# side_panel_V5_2.net
KiCad netlist of a schematic drawn in EAGLE
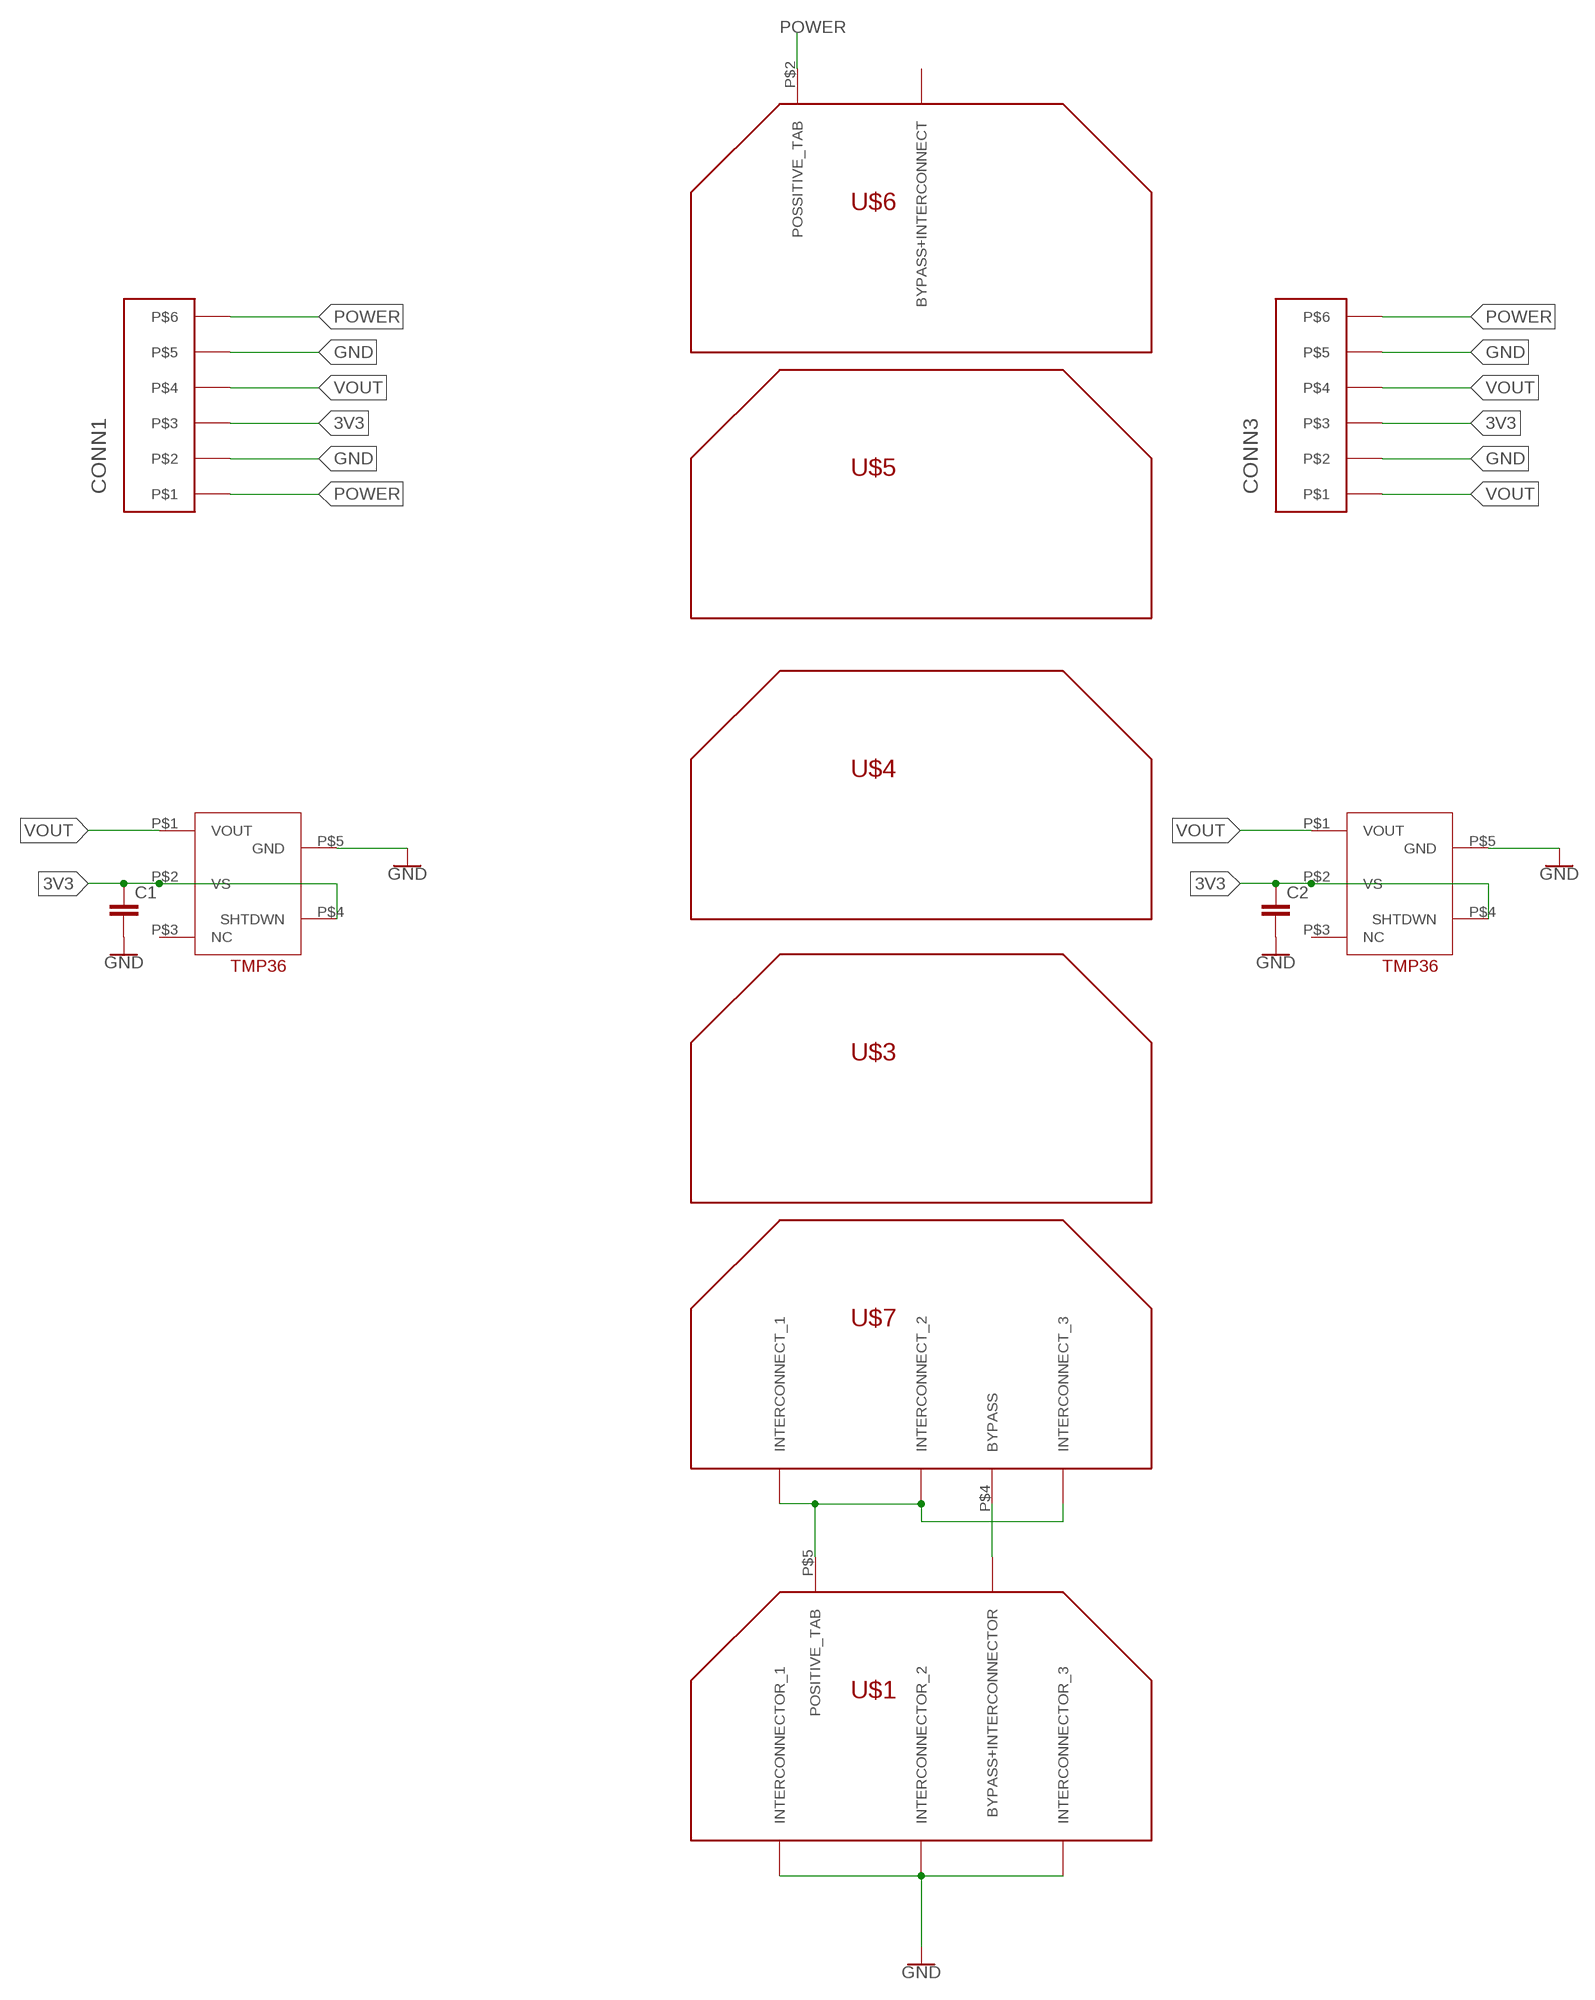
[diagram p0: schematic, sheet 1]

(export (version "E")
  (design (tool "Eeschema 10.0.6"))
  (components
    (comp (ref "C1")
      (value "CAPACITOR0805")
      (footprint "eagle-import:0805")
      (libsource (lib "eagle-import") (part "CAPACITOR0805"))
    )
    (comp (ref "C2")
      (value "CAPACITOR0805")
      (footprint "eagle-import:0805")
      (libsource (lib "eagle-import") (part "CAPACITOR0805"))
    )
    (comp (ref "CONN1")
      (value "PICOLOCK_6")
      (footprint "eagle-import:PICOLOCK_6")
      (libsource (lib "eagle-import") (part "PICOLOCK_6"))
    )
    (comp (ref "CONN3")
      (value "PICOLOCK_6")
      (footprint "eagle-import:PICOLOCK_6")
      (libsource (lib "eagle-import") (part "PICOLOCK_6"))
    )
    (comp (ref "U$1")
      (value "SOLAR_CELL_STAND-ALONE")
      (footprint "eagle-import:SOLAR_CELL_STAND-ALONE")
      (libsource (lib "eagle-import") (part "SOLAR_CELL_STAND-ALONE"))
    )
    (comp (ref "U$2")
      (value "TMP36")
      (footprint "eagle-import:SOT-23-5")
      (libsource (lib "eagle-import") (part "TMP36"))
    )
    (comp (ref "U$3")
      (value "SOALAR_CELL_OUTLINE")
      (footprint "eagle-import:SOLAR_CELL_OUTLINE")
      (libsource (lib "eagle-import") (part "SOALAR_CELL_OUTLINE"))
    )
    (comp (ref "U$4")
      (value "SOALAR_CELL_OUTLINE")
      (footprint "eagle-import:SOLAR_CELL_OUTLINE")
      (libsource (lib "eagle-import") (part "SOALAR_CELL_OUTLINE"))
    )
    (comp (ref "U$5")
      (value "SOALAR_CELL_OUTLINE")
      (footprint "eagle-import:SOLAR_CELL_OUTLINE")
      (libsource (lib "eagle-import") (part "SOALAR_CELL_OUTLINE"))
    )
    (comp (ref "U$6")
      (value "SOLAR_CELL_TOP")
      (footprint "eagle-import:SOLAR_CELL_TOP_SHORT-PAD")
      (libsource (lib "eagle-import") (part "SOLAR_CELL_TOP"))
    )
    (comp (ref "U$7")
      (value "SOLAR_CELL_BOTTOM+BYPASS")
      (footprint "eagle-import:SOLAR_CELL_BOTTOM+BYPASS")
      (libsource (lib "eagle-import") (part "SOLAR_CELL_BOTTOM+BYPASS"))
    )
    (comp (ref "U$8")
      (value "TMP36")
      (footprint "eagle-import:SOT-23-5")
      (libsource (lib "eagle-import") (part "TMP36"))
    )
  )
  (nets
    (net (code "1") (name "3V3") (class "Default")
      (node (ref "C1") (pin "1") (pinfunction "1_1") (pintype "passive"))
      (node (ref "C2") (pin "1") (pinfunction "1_1") (pintype "passive"))
      (node (ref "CONN1") (pin "P$3") (pinfunction "P$3_P$3") (pintype "bidirectional"))
      (node (ref "CONN3") (pin "P$3") (pinfunction "P$3_P$3") (pintype "bidirectional"))
      (node (ref "U$2") (pin "P$2") (pinfunction "VS_P$2") (pintype "bidirectional"))
      (node (ref "U$2") (pin "P$4") (pinfunction "SHTDWN_P$4") (pintype "bidirectional"))
      (node (ref "U$8") (pin "P$2") (pinfunction "VS_P$2") (pintype "bidirectional"))
      (node (ref "U$8") (pin "P$4") (pinfunction "SHTDWN_P$4") (pintype "bidirectional"))
    )
    (net (code "2") (name "GND") (class "Default")
      (node (ref "C1") (pin "2") (pinfunction "2_2") (pintype "passive"))
      (node (ref "C2") (pin "2") (pinfunction "2_2") (pintype "passive"))
      (node (ref "CONN1") (pin "P$2") (pinfunction "P$2_P$2") (pintype "bidirectional"))
      (node (ref "CONN1") (pin "P$5") (pinfunction "P$5_P$5") (pintype "bidirectional"))
      (node (ref "CONN3") (pin "P$2") (pinfunction "P$2_P$2") (pintype "bidirectional"))
      (node (ref "CONN3") (pin "P$5") (pinfunction "P$5_P$5") (pintype "bidirectional"))
      (node (ref "U$1") (pin "P$1") (pinfunction "INTERCONNECTOR_1_P$1") (pintype "bidirectional"))
      (node (ref "U$1") (pin "P$2") (pinfunction "INTERCONNECTOR_2_P$2") (pintype "bidirectional"))
      (node (ref "U$1") (pin "P$3") (pinfunction "INTERCONNECTOR_3_P$3") (pintype "bidirectional"))
      (node (ref "U$2") (pin "P$5") (pinfunction "GND_P$5") (pintype "bidirectional"))
      (node (ref "U$8") (pin "P$5") (pinfunction "GND_P$5") (pintype "bidirectional"))
    )
    (net (code "3") (name "Net-(U$1-BYPASS+INTERCONNECTOR)") (class "Default")
      (node (ref "U$1") (pin "P$4") (pinfunction "BYPASS+INTERCONNECTOR_P$4") (pintype "bidirectional"))
      (node (ref "U$7") (pin "P$4") (pinfunction "BYPASS_P$4") (pintype "bidirectional"))
    )
    (net (code "4") (name "Net-(U$1-POSITIVE_TAB)") (class "Default")
      (node (ref "U$1") (pin "P$5") (pinfunction "POSITIVE_TAB_P$5") (pintype "bidirectional"))
      (node (ref "U$7") (pin "P$1") (pinfunction "INTERCONNECT_1_P$1") (pintype "bidirectional"))
      (node (ref "U$7") (pin "P$2") (pinfunction "INTERCONNECT_2_P$2") (pintype "bidirectional"))
      (node (ref "U$7") (pin "P$3") (pinfunction "INTERCONNECT_3_P$3") (pintype "bidirectional"))
    )
    (net (code "5") (name "POWER") (class "Default")
      (node (ref "CONN1") (pin "P$1") (pinfunction "P$1_P$1") (pintype "bidirectional"))
      (node (ref "CONN1") (pin "P$6") (pinfunction "P$6_P$6") (pintype "bidirectional"))
      (node (ref "CONN3") (pin "P$6") (pinfunction "P$6_P$6") (pintype "bidirectional"))
      (node (ref "U$6") (pin "P$2") (pinfunction "POSSITIVE_TAB_P$2") (pintype "bidirectional"))
    )
    (net (code "6") (name "VOUT") (class "Default")
      (node (ref "CONN1") (pin "P$4") (pinfunction "P$4_P$4") (pintype "bidirectional"))
      (node (ref "CONN3") (pin "P$1") (pinfunction "P$1_P$1") (pintype "bidirectional"))
      (node (ref "CONN3") (pin "P$4") (pinfunction "P$4_P$4") (pintype "bidirectional"))
      (node (ref "U$2") (pin "P$1") (pinfunction "VOUT_P$1") (pintype "bidirectional"))
      (node (ref "U$8") (pin "P$1") (pinfunction "VOUT_P$1") (pintype "bidirectional"))
    )
    (net (code "7") (name "unconnected-(U$2-NC-PadP$3)") (class "Default")
      (node (ref "U$2") (pin "P$3") (pinfunction "NC_P$3") (pintype "bidirectional"))
    )
    (net (code "8") (name "unconnected-(U$6-BYPASS+INTERCONNECT-PadP$1)") (class "Default")
      (node (ref "U$6") (pin "P$1") (pinfunction "BYPASS+INTERCONNECT_P$1") (pintype "bidirectional"))
    )
    (net (code "9") (name "unconnected-(U$8-NC-PadP$3)") (class "Default")
      (node (ref "U$8") (pin "P$3") (pinfunction "NC_P$3") (pintype "bidirectional"))
    )
  )
)
